# phoenixRev2.net
KiCad netlist of a schematic drawn in EAGLE
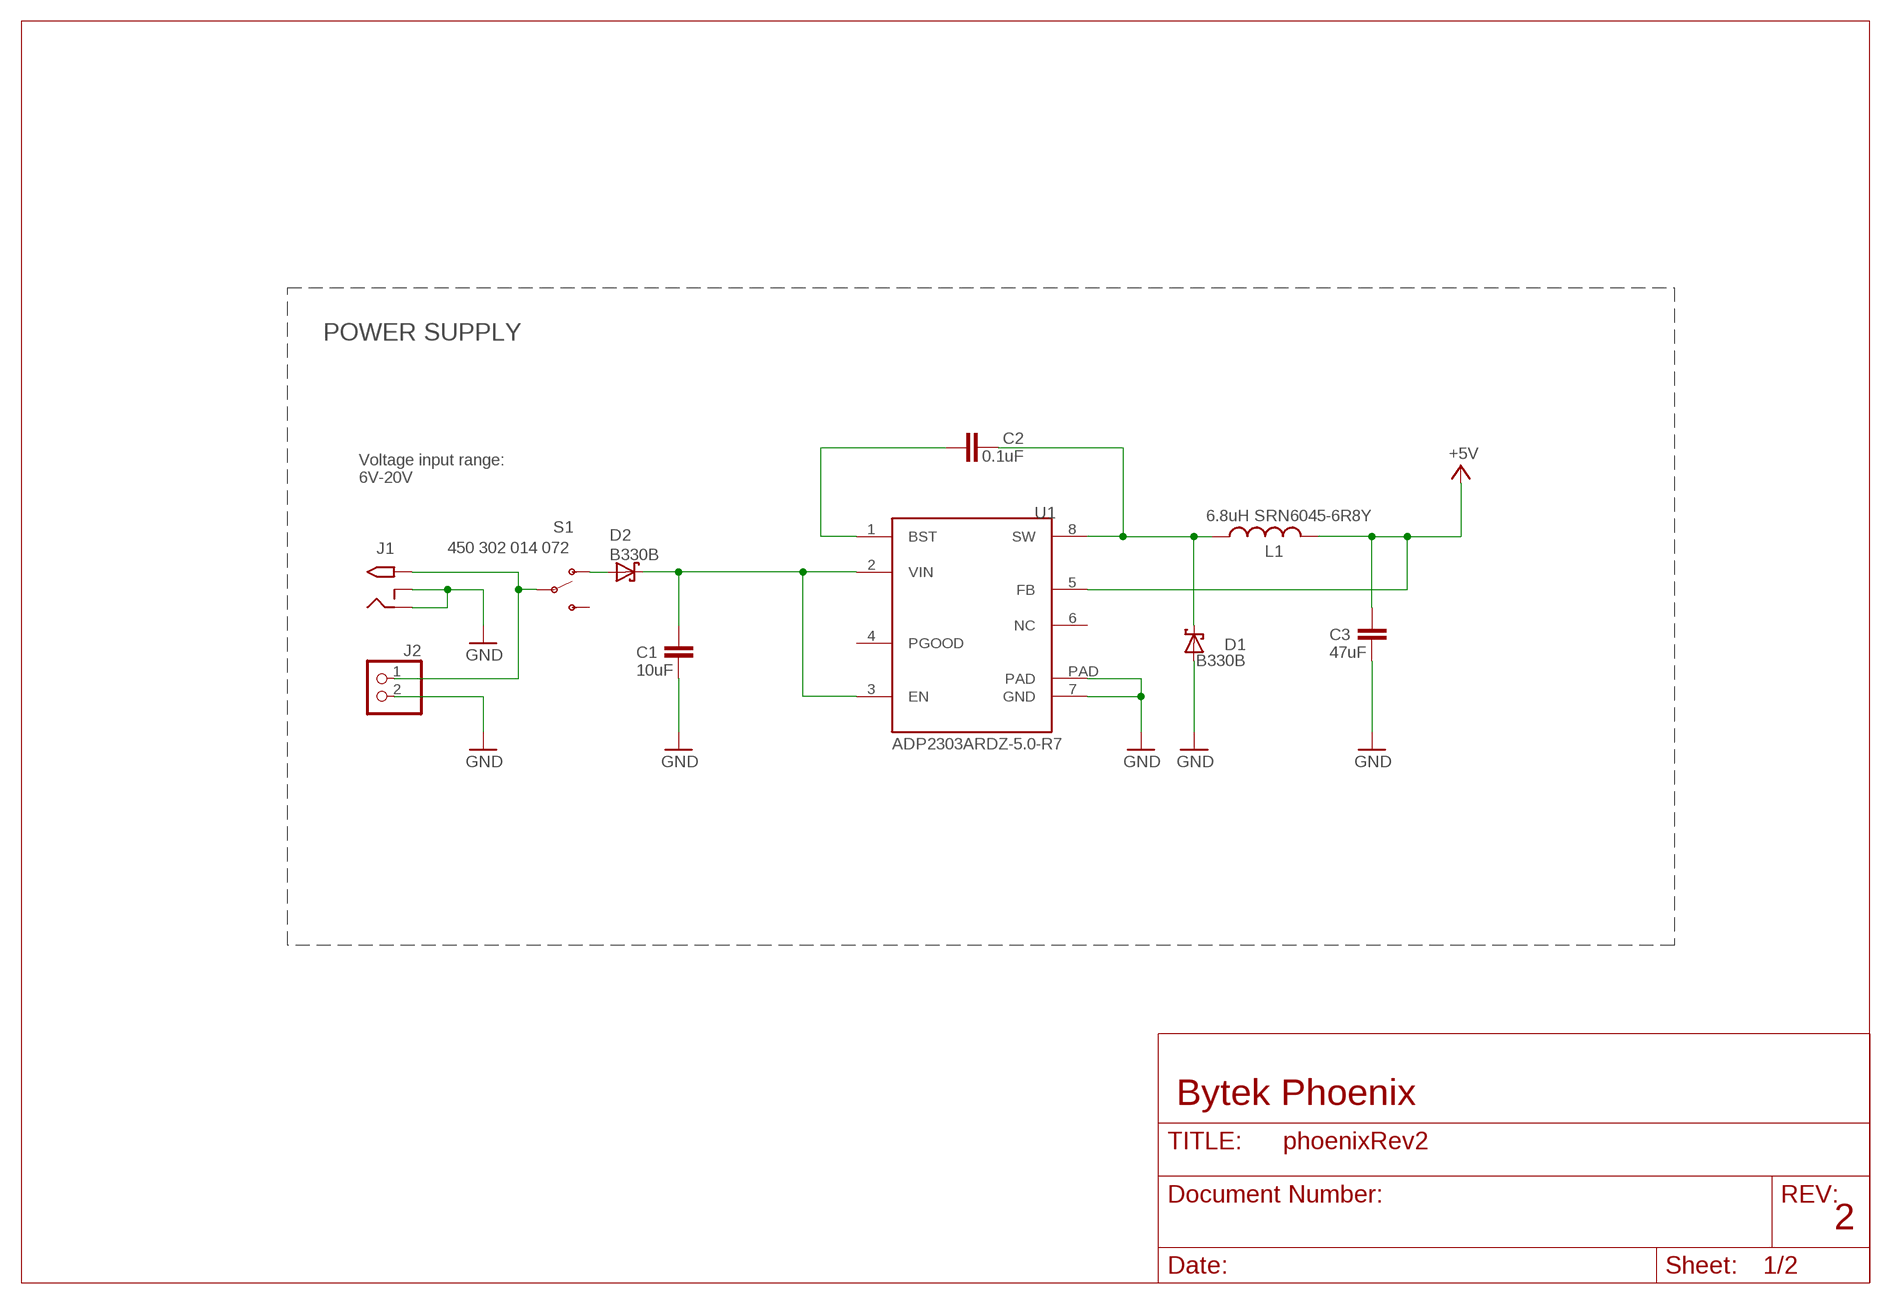
[diagram p0: schematic, sheet 1]
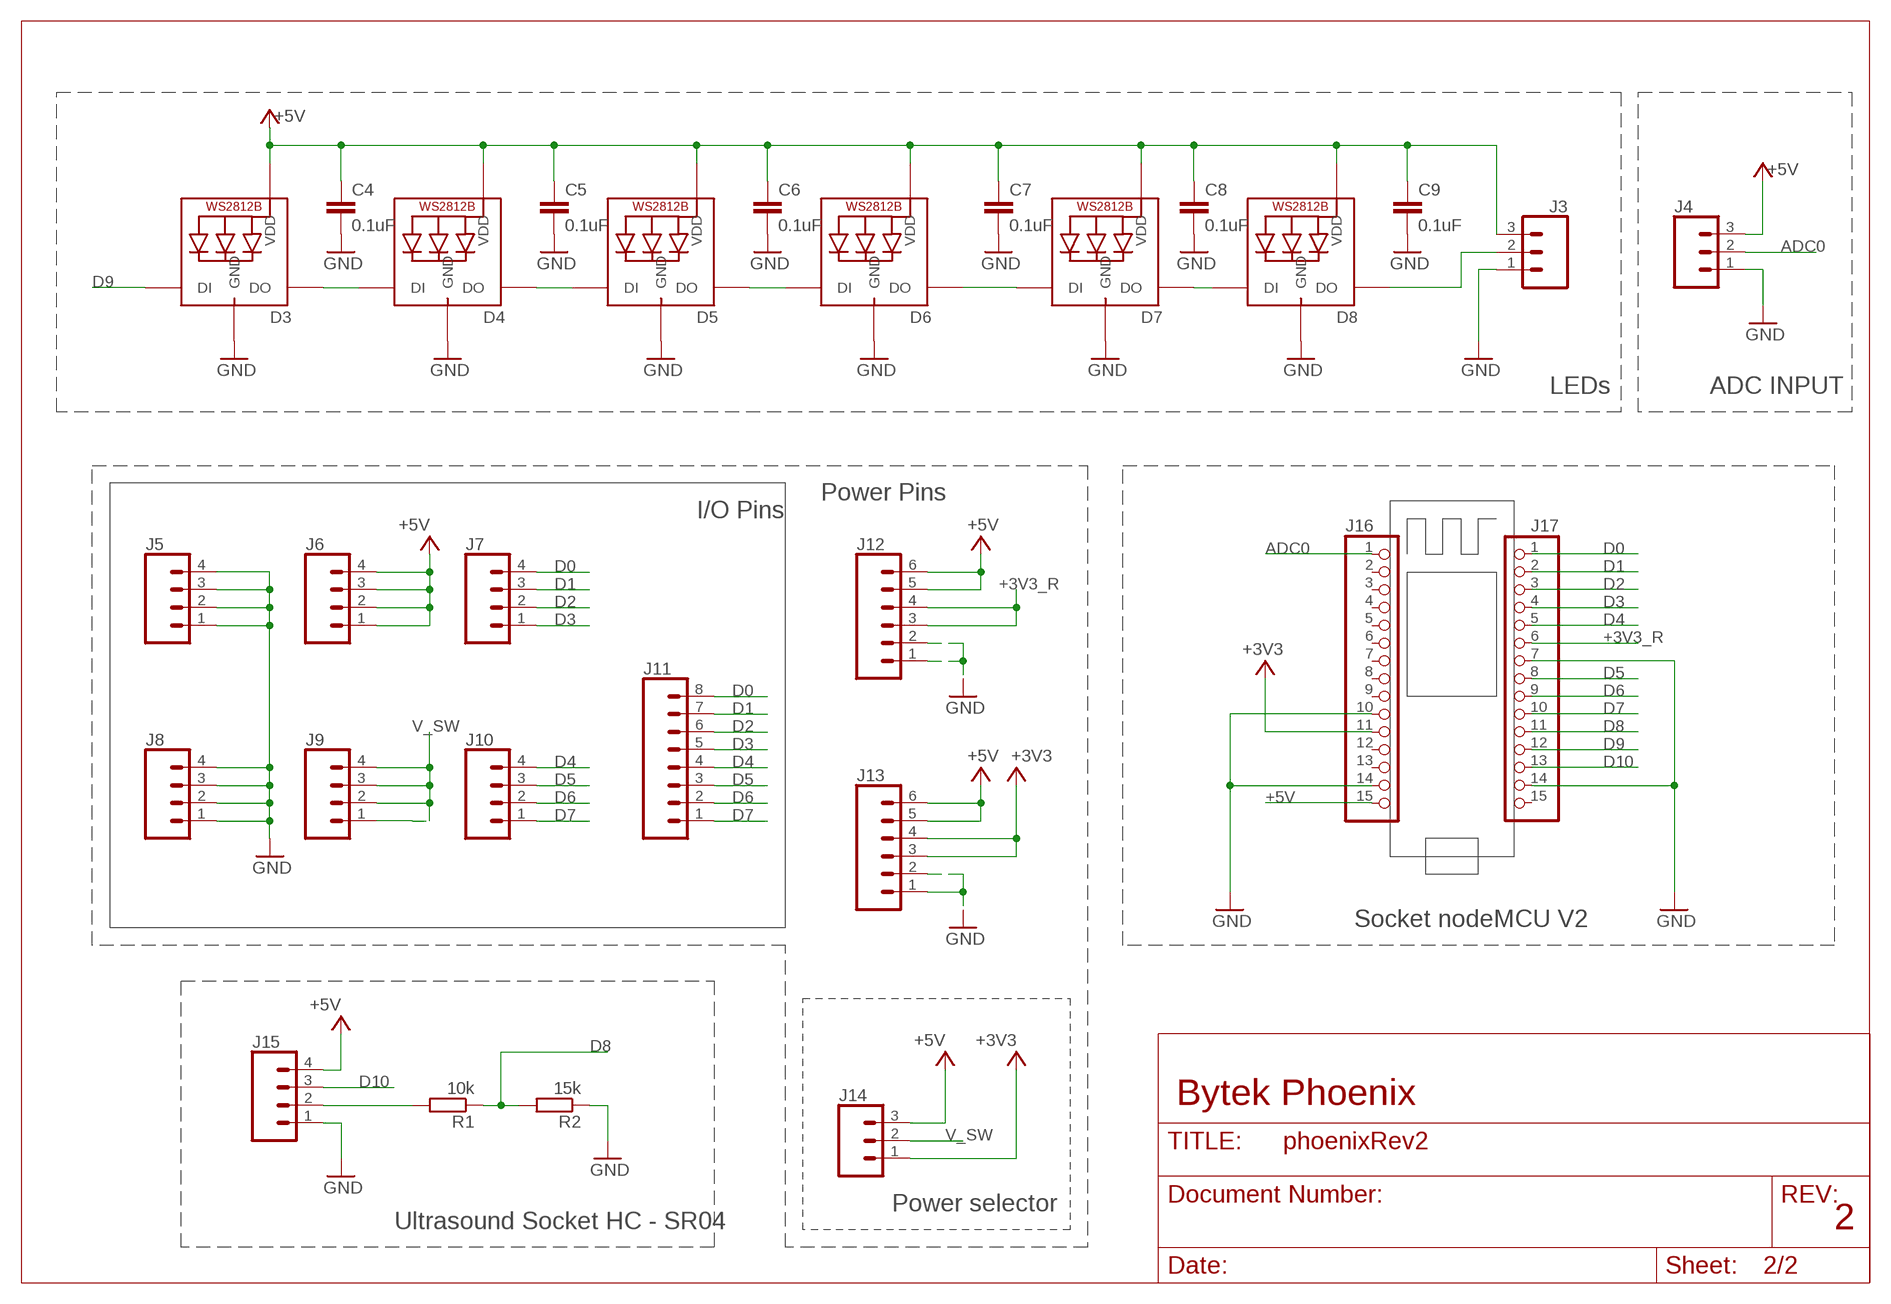
[diagram p1: schematic, sheet 2]

(export (version "E")
  (design (tool "Eeschema 10.0.6"))
  (components
    (comp (ref "C1")
      (value "10uF")
      (footprint "eagle-import:C0805")
      (libsource (lib "eagle-import") (part "C-EUC0805"))
    )
    (comp (ref "C2")
      (value "0.1uF")
      (footprint "eagle-import:C0805")
      (libsource (lib "eagle-import") (part "C-EUC0805"))
    )
    (comp (ref "C3")
      (value "47uF")
      (footprint "eagle-import:C1206")
      (libsource (lib "eagle-import") (part "C-EUC1206"))
    )
    (comp (ref "D1")
      (value "B330B")
      (footprint "eagle-import:SMB")
      (libsource (lib "eagle-import") (part "SCHOTTKY-DIODESMD"))
    )
    (comp (ref "D2")
      (value "B330B")
      (footprint "eagle-import:SMB")
      (libsource (lib "eagle-import") (part "SCHOTTKY-DIODESMD"))
    )
    (comp (ref "J1")
      (value "2.1MMJACKTHM")
      (footprint "eagle-import:PJ-102A")
      (libsource (lib "eagle-import") (part "2.1MMJACKTHM"))
    )
    (comp (ref "J2")
      (value "PINHD-1X2")
      (footprint "eagle-import:1X02")
      (libsource (lib "eagle-import") (part "PINHD-1X2"))
    )
    (comp (ref "L1")
      (value "6.8uH SRN6045-6R8Y")
      (footprint "eagle-import:POWER-CHOKE_WE-TPC")
      (libsource (lib "eagle-import") (part "L-USWE-TPC"))
    )
    (comp (ref "S1")
      (value "450 302 014 072")
      (footprint "eagle-import:SWITCH_SPDT_PTH_11.6X4.0MM")
      (libsource (lib "eagle-import") (part "SWITCH-SPDT-PTH-11.6X4.0MM"))
    )
    (comp (ref "U1")
      (value "ADP2303ARDZ-5.0-R7")
      (footprint "eagle-import:SO08_PAD")
      (libsource (lib "eagle-import") (part "ADP2303"))
    )
    (comp (ref "C4")
      (value "0.1uF")
      (footprint "eagle-import:C0805")
      (libsource (lib "eagle-import") (part "C-EUC0805"))
    )
    (comp (ref "C5")
      (value "0.1uF")
      (footprint "eagle-import:C0805")
      (libsource (lib "eagle-import") (part "C-EUC0805"))
    )
    (comp (ref "C6")
      (value "0.1uF")
      (footprint "eagle-import:C0805")
      (libsource (lib "eagle-import") (part "C-EUC0805"))
    )
    (comp (ref "C7")
      (value "0.1uF")
      (footprint "eagle-import:C0805")
      (libsource (lib "eagle-import") (part "C-EUC0805"))
    )
    (comp (ref "C8")
      (value "0.1uF")
      (footprint "eagle-import:C0805")
      (libsource (lib "eagle-import") (part "C-EUC0805"))
    )
    (comp (ref "C9")
      (value "0.1uF")
      (footprint "eagle-import:C0805")
      (libsource (lib "eagle-import") (part "C-EUC0805"))
    )
    (comp (ref "D3")
      (value "WS2812B5050")
      (footprint "eagle-import:WS2812B")
      (libsource (lib "eagle-import") (part "WS2812B5050"))
    )
    (comp (ref "D4")
      (value "WS2812B5050")
      (footprint "eagle-import:WS2812B")
      (libsource (lib "eagle-import") (part "WS2812B5050"))
    )
    (comp (ref "D5")
      (value "WS2812B5050")
      (footprint "eagle-import:WS2812B")
      (libsource (lib "eagle-import") (part "WS2812B5050"))
    )
    (comp (ref "D6")
      (value "WS2812B5050")
      (footprint "eagle-import:WS2812B")
      (libsource (lib "eagle-import") (part "WS2812B5050"))
    )
    (comp (ref "D7")
      (value "WS2812B5050")
      (footprint "eagle-import:WS2812B")
      (libsource (lib "eagle-import") (part "WS2812B5050"))
    )
    (comp (ref "D8")
      (value "WS2812B5050")
      (footprint "eagle-import:WS2812B")
      (libsource (lib "eagle-import") (part "WS2812B5050"))
    )
    (comp (ref "J3")
      (value "CONN_03")
      (footprint "eagle-import:1X03")
      (libsource (lib "eagle-import") (part "CONN_03"))
    )
    (comp (ref "J4")
      (value "CONN_03")
      (footprint "eagle-import:1X03")
      (libsource (lib "eagle-import") (part "CONN_03"))
    )
    (comp (ref "J5")
      (value "CONN_04")
      (footprint "eagle-import:1X04")
      (libsource (lib "eagle-import") (part "CONN_04"))
    )
    (comp (ref "J6")
      (value "CONN_04")
      (footprint "eagle-import:1X04")
      (libsource (lib "eagle-import") (part "CONN_04"))
    )
    (comp (ref "J7")
      (value "CONN_04")
      (footprint "eagle-import:1X04")
      (libsource (lib "eagle-import") (part "CONN_04"))
    )
    (comp (ref "J8")
      (value "CONN_04")
      (footprint "eagle-import:1X04")
      (libsource (lib "eagle-import") (part "CONN_04"))
    )
    (comp (ref "J9")
      (value "CONN_04")
      (footprint "eagle-import:1X04")
      (libsource (lib "eagle-import") (part "CONN_04"))
    )
    (comp (ref "J10")
      (value "CONN_04")
      (footprint "eagle-import:1X04")
      (libsource (lib "eagle-import") (part "CONN_04"))
    )
    (comp (ref "J11")
      (value "CONN_08\"")
      (footprint "eagle-import:1X08")
      (libsource (lib "eagle-import") (part "CONN_08{dblquote}"))
    )
    (comp (ref "J12")
      (value "CONN_06SILK_FEMALE_PTH")
      (footprint "eagle-import:1X06")
      (libsource (lib "eagle-import") (part "CONN_06SILK_FEMALE_PTH"))
    )
    (comp (ref "J13")
      (value "CONN_06SILK_FEMALE_PTH")
      (footprint "eagle-import:1X06")
      (libsource (lib "eagle-import") (part "CONN_06SILK_FEMALE_PTH"))
    )
    (comp (ref "J14")
      (value "CONN_03")
      (footprint "eagle-import:1X03")
      (libsource (lib "eagle-import") (part "CONN_03"))
    )
    (comp (ref "J15")
      (value "CONN_04")
      (footprint "eagle-import:1X04")
      (libsource (lib "eagle-import") (part "CONN_04"))
    )
    (comp (ref "J16")
      (value "PINHD-1X15-CB")
      (footprint "eagle-import:1X15-CB")
      (libsource (lib "eagle-import") (part "PINHD-1X15-CB"))
    )
    (comp (ref "J17")
      (value "PINHD-1X15-CB")
      (footprint "eagle-import:1X15-CB")
      (libsource (lib "eagle-import") (part "PINHD-1X15-CB"))
    )
    (comp (ref "R1")
      (value "10k")
      (footprint "eagle-import:R0805")
      (libsource (lib "eagle-import") (part "R-EU_R0805"))
    )
    (comp (ref "R2")
      (value "15k")
      (footprint "eagle-import:R0805")
      (libsource (lib "eagle-import") (part "R-EU_R0805"))
    )
  )
  (nets
    (net (code "1") (name "+3V3") (class "Default")
      (node (ref "J13") (pin "3") (pinfunction "3_3") (pintype "passive"))
      (node (ref "J13") (pin "4") (pinfunction "4_4") (pintype "passive"))
      (node (ref "J14") (pin "1") (pinfunction "1_1") (pintype "passive"))
      (node (ref "J16") (pin "11") (pinfunction "11_11") (pintype "passive"))
    )
    (net (code "2") (name "+3V3_R") (class "Default")
      (node (ref "J12") (pin "3") (pinfunction "3_3") (pintype "passive"))
      (node (ref "J12") (pin "4") (pinfunction "4_4") (pintype "passive"))
      (node (ref "J17") (pin "6") (pinfunction "6_6") (pintype "passive"))
    )
    (net (code "3") (name "+5V") (class "Default")
      (node (ref "C3") (pin "1") (pinfunction "1_1") (pintype "passive"))
      (node (ref "C4") (pin "1") (pinfunction "1_1") (pintype "passive"))
      (node (ref "C5") (pin "1") (pinfunction "1_1") (pintype "passive"))
      (node (ref "C6") (pin "1") (pinfunction "1_1") (pintype "passive"))
      (node (ref "C7") (pin "1") (pinfunction "1_1") (pintype "passive"))
      (node (ref "C8") (pin "1") (pinfunction "1_1") (pintype "passive"))
      (node (ref "C9") (pin "1") (pinfunction "1_1") (pintype "passive"))
      (node (ref "D3") (pin "1-VDD") (pinfunction "VDD_1-VDD") (pintype "power_in"))
      (node (ref "D4") (pin "1-VDD") (pinfunction "VDD_1-VDD") (pintype "power_in"))
      (node (ref "D5") (pin "1-VDD") (pinfunction "VDD_1-VDD") (pintype "power_in"))
      (node (ref "D6") (pin "1-VDD") (pinfunction "VDD_1-VDD") (pintype "power_in"))
      (node (ref "D7") (pin "1-VDD") (pinfunction "VDD_1-VDD") (pintype "power_in"))
      (node (ref "D8") (pin "1-VDD") (pinfunction "VDD_1-VDD") (pintype "power_in"))
      (node (ref "J12") (pin "5") (pinfunction "5_5") (pintype "passive"))
      (node (ref "J12") (pin "6") (pinfunction "6_6") (pintype "passive"))
      (node (ref "J13") (pin "5") (pinfunction "5_5") (pintype "passive"))
      (node (ref "J13") (pin "6") (pinfunction "6_6") (pintype "passive"))
      (node (ref "J14") (pin "3") (pinfunction "3_3") (pintype "passive"))
      (node (ref "J15") (pin "4") (pinfunction "4_4") (pintype "passive"))
      (node (ref "J16") (pin "15") (pinfunction "15_15") (pintype "passive"))
      (node (ref "J3") (pin "3") (pinfunction "3_3") (pintype "passive"))
      (node (ref "J4") (pin "3") (pinfunction "3_3") (pintype "passive"))
      (node (ref "J6") (pin "1") (pinfunction "1_1") (pintype "passive"))
      (node (ref "J6") (pin "2") (pinfunction "2_2") (pintype "passive"))
      (node (ref "J6") (pin "3") (pinfunction "3_3") (pintype "passive"))
      (node (ref "J6") (pin "4") (pinfunction "4_4") (pintype "passive"))
      (node (ref "L1") (pin "2") (pinfunction "2_2") (pintype "passive"))
      (node (ref "U1") (pin "5") (pinfunction "FB_5") (pintype "bidirectional"))
    )
    (net (code "4") (name "ADC0") (class "Default")
      (node (ref "J16") (pin "1") (pinfunction "1_1") (pintype "passive"))
      (node (ref "J4") (pin "2") (pinfunction "2_2") (pintype "passive"))
    )
    (net (code "5") (name "D0") (class "Default")
      (node (ref "J11") (pin "8") (pinfunction "8_8") (pintype "passive"))
      (node (ref "J17") (pin "1") (pinfunction "1_1") (pintype "passive"))
      (node (ref "J7") (pin "4") (pinfunction "4_4") (pintype "passive"))
    )
    (net (code "6") (name "D1") (class "Default")
      (node (ref "J11") (pin "7") (pinfunction "7_7") (pintype "passive"))
      (node (ref "J17") (pin "2") (pinfunction "2_2") (pintype "passive"))
      (node (ref "J7") (pin "3") (pinfunction "3_3") (pintype "passive"))
    )
    (net (code "7") (name "D2") (class "Default")
      (node (ref "J11") (pin "6") (pinfunction "6_6") (pintype "passive"))
      (node (ref "J17") (pin "3") (pinfunction "3_3") (pintype "passive"))
      (node (ref "J7") (pin "2") (pinfunction "2_2") (pintype "passive"))
    )
    (net (code "8") (name "D3") (class "Default")
      (node (ref "J11") (pin "5") (pinfunction "5_5") (pintype "passive"))
      (node (ref "J17") (pin "4") (pinfunction "4_4") (pintype "passive"))
      (node (ref "J7") (pin "1") (pinfunction "1_1") (pintype "passive"))
    )
    (net (code "9") (name "D4") (class "Default")
      (node (ref "J10") (pin "4") (pinfunction "4_4") (pintype "passive"))
      (node (ref "J11") (pin "4") (pinfunction "4_4") (pintype "passive"))
      (node (ref "J17") (pin "5") (pinfunction "5_5") (pintype "passive"))
    )
    (net (code "10") (name "D5") (class "Default")
      (node (ref "J10") (pin "3") (pinfunction "3_3") (pintype "passive"))
      (node (ref "J11") (pin "3") (pinfunction "3_3") (pintype "passive"))
      (node (ref "J17") (pin "8") (pinfunction "8_8") (pintype "passive"))
    )
    (net (code "11") (name "D6") (class "Default")
      (node (ref "J10") (pin "2") (pinfunction "2_2") (pintype "passive"))
      (node (ref "J11") (pin "2") (pinfunction "2_2") (pintype "passive"))
      (node (ref "J17") (pin "9") (pinfunction "9_9") (pintype "passive"))
    )
    (net (code "12") (name "D7") (class "Default")
      (node (ref "J10") (pin "1") (pinfunction "1_1") (pintype "passive"))
      (node (ref "J11") (pin "1") (pinfunction "1_1") (pintype "passive"))
      (node (ref "J17") (pin "10") (pinfunction "10_10") (pintype "passive"))
    )
    (net (code "13") (name "D8") (class "Default")
      (node (ref "J17") (pin "11") (pinfunction "11_11") (pintype "passive"))
      (node (ref "R1") (pin "1") (pinfunction "1_1") (pintype "passive"))
      (node (ref "R2") (pin "2") (pinfunction "2_2") (pintype "passive"))
    )
    (net (code "14") (name "D9") (class "Default")
      (node (ref "D3") (pin "4-DIN") (pinfunction "DI_4-DIN") (pintype "input"))
      (node (ref "J17") (pin "12") (pinfunction "12_12") (pintype "passive"))
    )
    (net (code "15") (name "D10") (class "Default")
      (node (ref "J15") (pin "3") (pinfunction "3_3") (pintype "passive"))
      (node (ref "J17") (pin "13") (pinfunction "13_13") (pintype "passive"))
    )
    (net (code "16") (name "GND") (class "Default")
      (node (ref "C1") (pin "2") (pinfunction "2_2") (pintype "passive"))
      (node (ref "C3") (pin "2") (pinfunction "2_2") (pintype "passive"))
      (node (ref "C4") (pin "2") (pinfunction "2_2") (pintype "passive"))
      (node (ref "C5") (pin "2") (pinfunction "2_2") (pintype "passive"))
      (node (ref "C6") (pin "2") (pinfunction "2_2") (pintype "passive"))
      (node (ref "C7") (pin "2") (pinfunction "2_2") (pintype "passive"))
      (node (ref "C8") (pin "2") (pinfunction "2_2") (pintype "passive"))
      (node (ref "C9") (pin "2") (pinfunction "2_2") (pintype "passive"))
      (node (ref "D1") (pin "A") (pinfunction "A_A") (pintype "passive"))
      (node (ref "D3") (pin "3-GND") (pinfunction "GND_3-GND") (pintype "power_in"))
      (node (ref "D4") (pin "3-GND") (pinfunction "GND_3-GND") (pintype "power_in"))
      (node (ref "D5") (pin "3-GND") (pinfunction "GND_3-GND") (pintype "power_in"))
      (node (ref "D6") (pin "3-GND") (pinfunction "GND_3-GND") (pintype "power_in"))
      (node (ref "D7") (pin "3-GND") (pinfunction "GND_3-GND") (pintype "power_in"))
      (node (ref "D8") (pin "3-GND") (pinfunction "GND_3-GND") (pintype "power_in"))
      (node (ref "J1") (pin "RING") (pinfunction "RING_RING") (pintype "bidirectional"))
      (node (ref "J1") (pin "RING_SW") (pinfunction "RING_SW_RING_SW") (pintype "bidirectional"))
      (node (ref "J12") (pin "1") (pinfunction "1_1") (pintype "passive"))
      (node (ref "J12") (pin "2") (pinfunction "2_2") (pintype "passive"))
      (node (ref "J13") (pin "1") (pinfunction "1_1") (pintype "passive"))
      (node (ref "J13") (pin "2") (pinfunction "2_2") (pintype "passive"))
      (node (ref "J15") (pin "1") (pinfunction "1_1") (pintype "passive"))
      (node (ref "J16") (pin "10") (pinfunction "10_10") (pintype "passive"))
      (node (ref "J16") (pin "14") (pinfunction "14_14") (pintype "passive"))
      (node (ref "J17") (pin "14") (pinfunction "14_14") (pintype "passive"))
      (node (ref "J17") (pin "7") (pinfunction "7_7") (pintype "passive"))
      (node (ref "J2") (pin "2") (pinfunction "2_2") (pintype "passive"))
      (node (ref "J3") (pin "1") (pinfunction "1_1") (pintype "passive"))
      (node (ref "J4") (pin "1") (pinfunction "1_1") (pintype "passive"))
      (node (ref "J5") (pin "1") (pinfunction "1_1") (pintype "passive"))
      (node (ref "J5") (pin "2") (pinfunction "2_2") (pintype "passive"))
      (node (ref "J5") (pin "3") (pinfunction "3_3") (pintype "passive"))
      (node (ref "J5") (pin "4") (pinfunction "4_4") (pintype "passive"))
      (node (ref "J8") (pin "1") (pinfunction "1_1") (pintype "passive"))
      (node (ref "J8") (pin "2") (pinfunction "2_2") (pintype "passive"))
      (node (ref "J8") (pin "3") (pinfunction "3_3") (pintype "passive"))
      (node (ref "J8") (pin "4") (pinfunction "4_4") (pintype "passive"))
      (node (ref "R2") (pin "1") (pinfunction "1_1") (pintype "passive"))
      (node (ref "U1") (pin "7") (pinfunction "GND_7") (pintype "bidirectional"))
      (node (ref "U1") (pin "PAD") (pinfunction "PAD_PAD") (pintype "bidirectional"))
    )
    (net (code "17") (name "Net-(D3-DO)") (class "Default")
      (node (ref "D3") (pin "2-DOUT") (pinfunction "DO_2-DOUT") (pintype "output"))
      (node (ref "D4") (pin "4-DIN") (pinfunction "DI_4-DIN") (pintype "input"))
    )
    (net (code "18") (name "Net-(D4-DO)") (class "Default")
      (node (ref "D4") (pin "2-DOUT") (pinfunction "DO_2-DOUT") (pintype "output"))
      (node (ref "D5") (pin "4-DIN") (pinfunction "DI_4-DIN") (pintype "input"))
    )
    (net (code "19") (name "Net-(D5-DO)") (class "Default")
      (node (ref "D5") (pin "2-DOUT") (pinfunction "DO_2-DOUT") (pintype "output"))
      (node (ref "D6") (pin "4-DIN") (pinfunction "DI_4-DIN") (pintype "input"))
    )
    (net (code "20") (name "Net-(D6-DO)") (class "Default")
      (node (ref "D6") (pin "2-DOUT") (pinfunction "DO_2-DOUT") (pintype "output"))
      (node (ref "D7") (pin "4-DIN") (pinfunction "DI_4-DIN") (pintype "input"))
    )
    (net (code "21") (name "Net-(D7-DO)") (class "Default")
      (node (ref "D7") (pin "2-DOUT") (pinfunction "DO_2-DOUT") (pintype "output"))
      (node (ref "D8") (pin "4-DIN") (pinfunction "DI_4-DIN") (pintype "input"))
    )
    (net (code "22") (name "Net-(D8-DO)") (class "Default")
      (node (ref "D8") (pin "2-DOUT") (pinfunction "DO_2-DOUT") (pintype "output"))
      (node (ref "J3") (pin "2") (pinfunction "2_2") (pintype "passive"))
    )
    (net (code "23") (name "Net-(J15-Pad2)") (class "Default")
      (node (ref "J15") (pin "2") (pinfunction "2_2") (pintype "passive"))
      (node (ref "R1") (pin "2") (pinfunction "2_2") (pintype "passive"))
    )
    (net (code "24") (name "Net-(S1-O)") (class "Default")
      (node (ref "D2") (pin "A") (pinfunction "A_A") (pintype "passive"))
      (node (ref "S1") (pin "1") (pinfunction "O_1") (pintype "passive"))
    )
    (net (code "25") (name "Net-(S1-P)") (class "Default")
      (node (ref "J1") (pin "TIP") (pinfunction "TIP_TIP") (pintype "bidirectional"))
      (node (ref "J2") (pin "1") (pinfunction "1_1") (pintype "passive"))
      (node (ref "S1") (pin "2") (pinfunction "P_2") (pintype "passive"))
    )
    (net (code "26") (name "Net-(U1-BST)") (class "Default")
      (node (ref "C2") (pin "1") (pinfunction "1_1") (pintype "passive"))
      (node (ref "U1") (pin "1") (pinfunction "BST_1") (pintype "bidirectional"))
    )
    (net (code "27") (name "Net-(U1-EN)") (class "Default")
      (node (ref "C1") (pin "1") (pinfunction "1_1") (pintype "passive"))
      (node (ref "D2") (pin "C") (pinfunction "C_C") (pintype "passive"))
      (node (ref "U1") (pin "2") (pinfunction "VIN_2") (pintype "bidirectional"))
      (node (ref "U1") (pin "3") (pinfunction "EN_3") (pintype "bidirectional"))
    )
    (net (code "28") (name "Net-(U1-SW)") (class "Default")
      (node (ref "C2") (pin "2") (pinfunction "2_2") (pintype "passive"))
      (node (ref "D1") (pin "C") (pinfunction "C_C") (pintype "passive"))
      (node (ref "L1") (pin "1") (pinfunction "1_1") (pintype "passive"))
      (node (ref "U1") (pin "8") (pinfunction "SW_8") (pintype "bidirectional"))
    )
    (net (code "29") (name "V_SW") (class "Default")
      (node (ref "J14") (pin "2") (pinfunction "2_2") (pintype "passive"))
      (node (ref "J9") (pin "1") (pinfunction "1_1") (pintype "passive"))
      (node (ref "J9") (pin "2") (pinfunction "2_2") (pintype "passive"))
      (node (ref "J9") (pin "3") (pinfunction "3_3") (pintype "passive"))
      (node (ref "J9") (pin "4") (pinfunction "4_4") (pintype "passive"))
    )
    (net (code "30") (name "unconnected-(J16-Pad2)") (class "Default")
      (node (ref "J16") (pin "2") (pinfunction "2_2") (pintype "passive"))
    )
    (net (code "31") (name "unconnected-(J16-Pad3)") (class "Default")
      (node (ref "J16") (pin "3") (pinfunction "3_3") (pintype "passive"))
    )
    (net (code "32") (name "unconnected-(J16-Pad4)") (class "Default")
      (node (ref "J16") (pin "4") (pinfunction "4_4") (pintype "passive"))
    )
    (net (code "33") (name "unconnected-(J16-Pad5)") (class "Default")
      (node (ref "J16") (pin "5") (pinfunction "5_5") (pintype "passive"))
    )
    (net (code "34") (name "unconnected-(J16-Pad6)") (class "Default")
      (node (ref "J16") (pin "6") (pinfunction "6_6") (pintype "passive"))
    )
    (net (code "35") (name "unconnected-(J16-Pad7)") (class "Default")
      (node (ref "J16") (pin "7") (pinfunction "7_7") (pintype "passive"))
    )
    (net (code "36") (name "unconnected-(J16-Pad8)") (class "Default")
      (node (ref "J16") (pin "8") (pinfunction "8_8") (pintype "passive"))
    )
    (net (code "37") (name "unconnected-(J16-Pad9)") (class "Default")
      (node (ref "J16") (pin "9") (pinfunction "9_9") (pintype "passive"))
    )
    (net (code "38") (name "unconnected-(J16-Pad12)") (class "Default")
      (node (ref "J16") (pin "12") (pinfunction "12_12") (pintype "passive"))
    )
    (net (code "39") (name "unconnected-(J16-Pad13)") (class "Default")
      (node (ref "J16") (pin "13") (pinfunction "13_13") (pintype "passive"))
    )
    (net (code "40") (name "unconnected-(J17-Pad15)") (class "Default")
      (node (ref "J17") (pin "15") (pinfunction "15_15") (pintype "passive"))
    )
    (net (code "41") (name "unconnected-(S1-S-Pad3)") (class "Default")
      (node (ref "S1") (pin "3") (pinfunction "S_3") (pintype "passive"))
    )
    (net (code "42") (name "unconnected-(U1-NC-Pad6)") (class "Default")
      (node (ref "U1") (pin "6") (pinfunction "NC_6") (pintype "bidirectional"))
    )
    (net (code "43") (name "unconnected-(U1-PGOOD-Pad4)") (class "Default")
      (node (ref "U1") (pin "4") (pinfunction "PGOOD_4") (pintype "bidirectional"))
    )
  )
)
